# power_jack.net
KiCad netlist of a schematic drawn in EAGLE
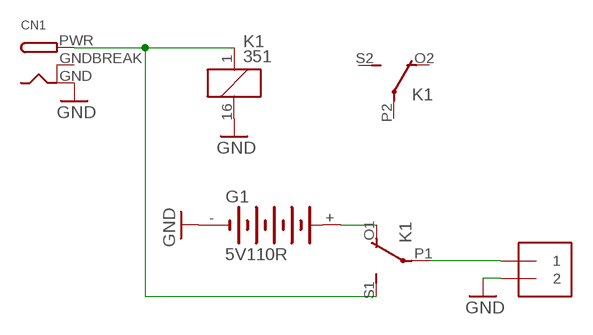
[diagram p0: schematic, sheet 1]

(export (version "E")
  (design (tool "Eeschema 10.0.6"))
  (components
    (comp (ref "CN1")
      (value "DCBARRELPTH")
      (footprint "eagle-import:DCJACK_2MM_PTH")
      (libsource (lib "eagle-import") (part "DCBARRELPTH"))
    )
    (comp (ref "G1")
      (value "5V110R")
      (footprint "eagle-import:5V110R")
      (libsource (lib "eagle-import") (part "5V110R"))
    )
    (comp (ref "K1")
      (value "351")
      (footprint "eagle-import:351")
      (libsource (lib "eagle-import") (part "351"))
    )
    (comp (ref "PI")
      (value "1X2-3.5MM")
      (footprint "eagle-import:1X2-3.5MM")
      (libsource (lib "eagle-import") (part "1X2-3.5MM"))
    )
  )
  (nets
    (net (code "1") (name "/GNDBREAK") (class "Default")
      (node (ref "CN1") (pin "GNDBREAK") (pinfunction "GNDBREAK_GNDBREAK") (pintype "power_in"))
    )
    (net (code "2") (name "GND") (class "Default")
      (node (ref "CN1") (pin "GND") (pinfunction "GND_GND") (pintype "power_in"))
      (node (ref "G1") (pin "-") (pinfunction "-_-") (pintype "passive"))
      (node (ref "K1") (pin "16") (pinfunction "2_16") (pintype "passive"))
      (node (ref "PI") (pin "2") (pinfunction "2_2") (pintype "passive"))
    )
    (net (code "3") (name "Net-(K1B-O)") (class "Default")
      (node (ref "G1") (pin "+") (pinfunction "+_+") (pintype "passive"))
      (node (ref "K1") (pin "O1") (pinfunction "O_O1") (pintype "passive"))
    )
    (net (code "4") (name "Net-(K1B-P)") (class "Default")
      (node (ref "K1") (pin "P1") (pinfunction "P_P1") (pintype "passive"))
      (node (ref "PI") (pin "1") (pinfunction "1_1") (pintype "passive"))
    )
    (net (code "5") (name "Net-(K1B-S)") (class "Default")
      (node (ref "CN1") (pin "PWR") (pinfunction "PWR_PWR") (pintype "power_in"))
      (node (ref "K1") (pin "1") (pinfunction "1_1") (pintype "passive"))
      (node (ref "K1") (pin "S1") (pinfunction "S_S1") (pintype "passive"))
    )
    (net (code "6") (name "unconnected-(G1-+-Pad+@1)") (class "Default")
      (node (ref "G1") (pin "+@1") (pinfunction "+_+@1") (pintype "passive"))
    )
    (net (code "7") (name "unconnected-(K1C-O-PadO2)") (class "Default")
      (node (ref "K1") (pin "O2") (pinfunction "O_O2") (pintype "passive"))
    )
    (net (code "8") (name "unconnected-(K1C-P-PadP2)") (class "Default")
      (node (ref "K1") (pin "P2") (pinfunction "P_P2") (pintype "passive"))
    )
    (net (code "9") (name "unconnected-(K1C-S-PadS2)") (class "Default")
      (node (ref "K1") (pin "S2") (pinfunction "S_S2") (pintype "passive"))
    )
  )
)
